# voice_board_kombi.net
KiCad netlist of a schematic drawn in EAGLE
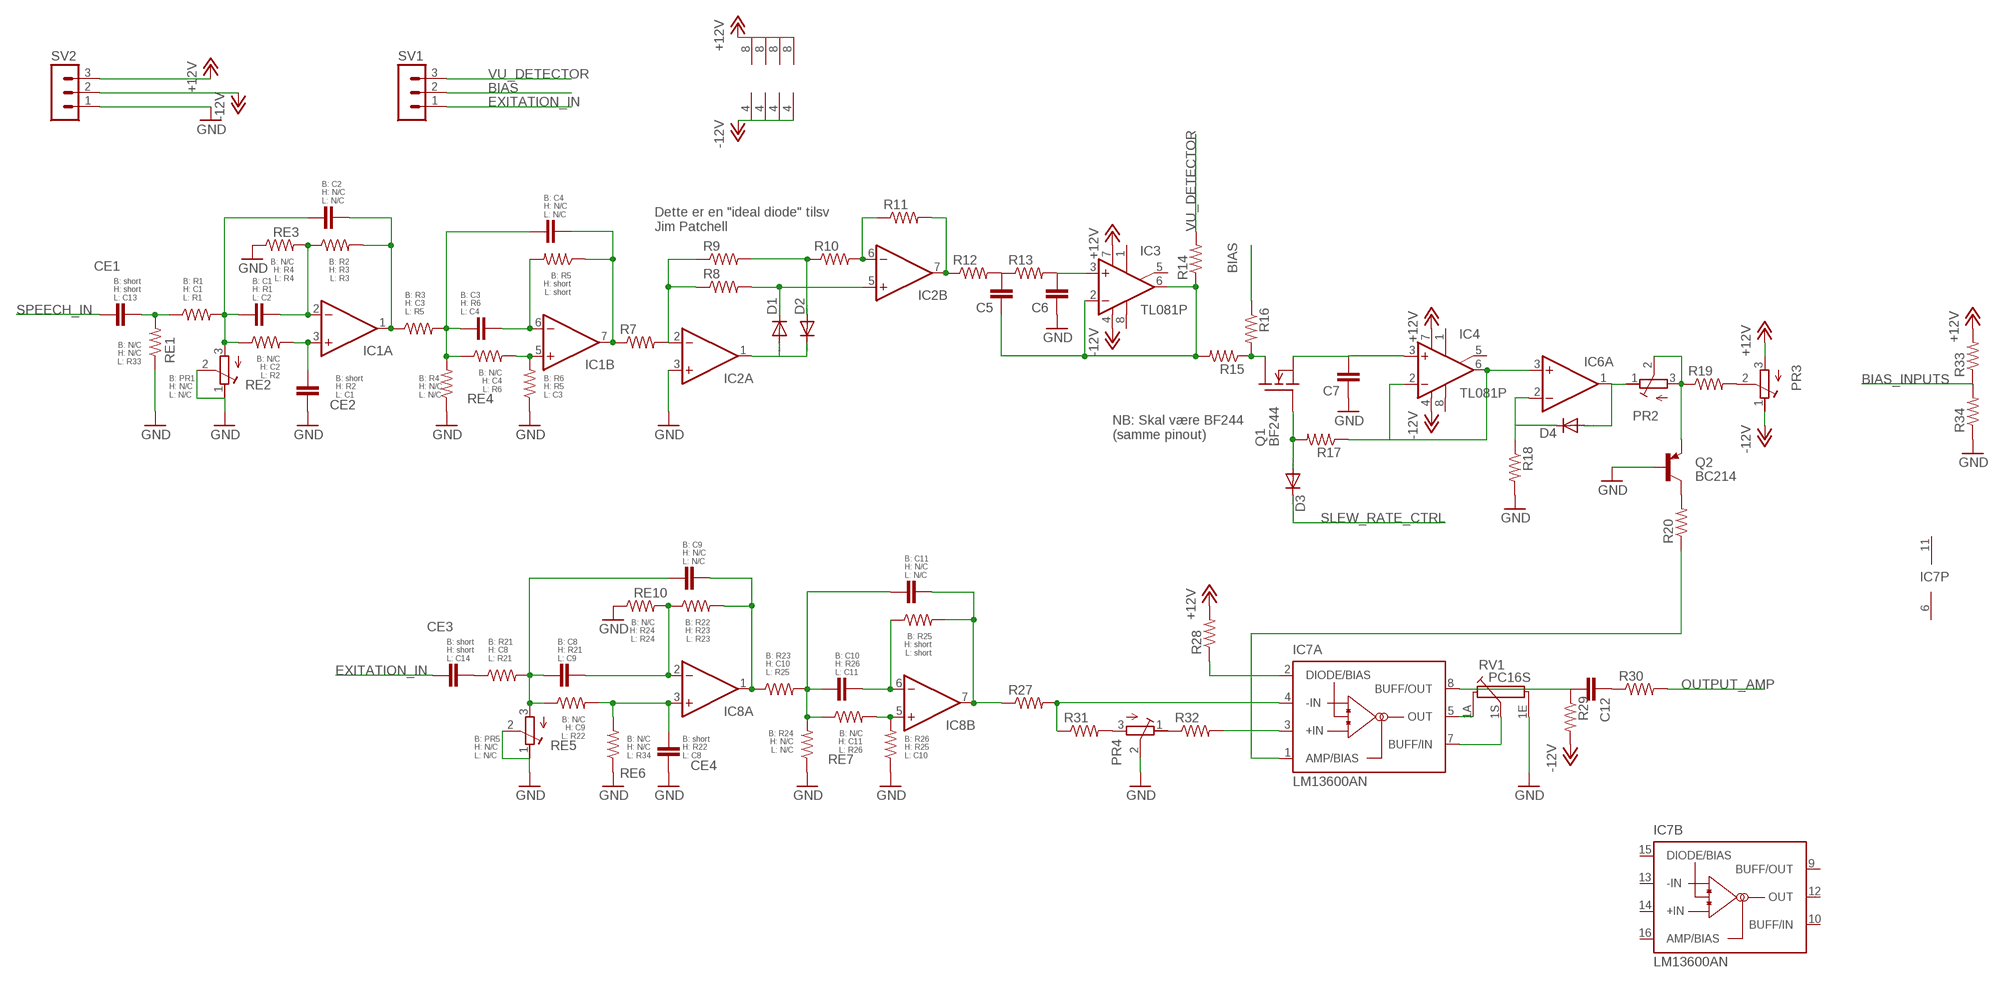
[diagram p0: schematic, sheet 1]

(export (version "E")
  (design (tool "Eeschema 10.0.6"))
  (components
    (comp (ref "C1")
      (value "C-EU050-025X075")
      (footprint "eagle-import:C050-025X075")
      (libsource (lib "eagle-import") (part "C-EU050-025X075"))
    )
    (comp (ref "C2")
      (value "C-EU050-025X075")
      (footprint "eagle-import:C050-025X075")
      (libsource (lib "eagle-import") (part "C-EU050-025X075"))
    )
    (comp (ref "C3")
      (value "C-EU050-025X075")
      (footprint "eagle-import:C050-025X075")
      (libsource (lib "eagle-import") (part "C-EU050-025X075"))
    )
    (comp (ref "C4")
      (value "C-EU050-025X075")
      (footprint "eagle-import:C050-025X075")
      (libsource (lib "eagle-import") (part "C-EU050-025X075"))
    )
    (comp (ref "C5")
      (value "C-EU050-025X075")
      (footprint "eagle-import:C050-025X075")
      (libsource (lib "eagle-import") (part "C-EU050-025X075"))
    )
    (comp (ref "C6")
      (value "C-EU050-025X075")
      (footprint "eagle-import:C050-025X075")
      (libsource (lib "eagle-import") (part "C-EU050-025X075"))
    )
    (comp (ref "C7")
      (value "C-EU050-025X075")
      (footprint "eagle-import:C050-025X075")
      (libsource (lib "eagle-import") (part "C-EU050-025X075"))
    )
    (comp (ref "C8")
      (value "C-EU050-025X075")
      (footprint "eagle-import:C050-025X075")
      (libsource (lib "eagle-import") (part "C-EU050-025X075"))
    )
    (comp (ref "C9")
      (value "C-EU050-025X075")
      (footprint "eagle-import:C050-025X075")
      (libsource (lib "eagle-import") (part "C-EU050-025X075"))
    )
    (comp (ref "C10")
      (value "C-EU050-025X075")
      (footprint "eagle-import:C050-025X075")
      (libsource (lib "eagle-import") (part "C-EU050-025X075"))
    )
    (comp (ref "C11")
      (value "C-EU050-025X075")
      (footprint "eagle-import:C050-025X075")
      (libsource (lib "eagle-import") (part "C-EU050-025X075"))
    )
    (comp (ref "C12")
      (value "C-EU050-025X075")
      (footprint "eagle-import:C050-025X075")
      (libsource (lib "eagle-import") (part "C-EU050-025X075"))
    )
    (comp (ref "CE1")
      (value "C-EU050-025X075")
      (footprint "eagle-import:C050-025X075")
      (libsource (lib "eagle-import") (part "C-EU050-025X075"))
    )
    (comp (ref "CE2")
      (value "C-EU050-025X075")
      (footprint "eagle-import:C050-025X075")
      (libsource (lib "eagle-import") (part "C-EU050-025X075"))
    )
    (comp (ref "CE3")
      (value "C-EU050-025X075")
      (footprint "eagle-import:C050-025X075")
      (libsource (lib "eagle-import") (part "C-EU050-025X075"))
    )
    (comp (ref "CE4")
      (value "C-EU050-025X075")
      (footprint "eagle-import:C050-025X075")
      (libsource (lib "eagle-import") (part "C-EU050-025X075"))
    )
    (comp (ref "D1")
      (value "DIODE-D-5")
      (footprint "eagle-import:D-5")
      (libsource (lib "eagle-import") (part "DIODE-D-5"))
    )
    (comp (ref "D2")
      (value "DIODE-D-5")
      (footprint "eagle-import:D-5")
      (libsource (lib "eagle-import") (part "DIODE-D-5"))
    )
    (comp (ref "D3")
      (value "DIODE-D-5")
      (footprint "eagle-import:D-5")
      (libsource (lib "eagle-import") (part "DIODE-D-5"))
    )
    (comp (ref "D4")
      (value "DIODE-D-5")
      (footprint "eagle-import:D-5")
      (libsource (lib "eagle-import") (part "DIODE-D-5"))
    )
    (comp (ref "IC1")
      (value "TL072P")
      (footprint "eagle-import:DIL08")
      (libsource (lib "eagle-import") (part "TL072P"))
    )
    (comp (ref "IC2")
      (value "TL072P")
      (footprint "eagle-import:DIL08")
      (libsource (lib "eagle-import") (part "TL072P"))
    )
    (comp (ref "IC3")
      (value "TL081P")
      (footprint "eagle-import:DIL08")
      (libsource (lib "eagle-import") (part "TL081P"))
    )
    (comp (ref "IC4")
      (value "TL081P")
      (footprint "eagle-import:DIL08")
      (libsource (lib "eagle-import") (part "TL081P"))
    )
    (comp (ref "IC6")
      (value "TL072P")
      (footprint "eagle-import:DIL08")
      (libsource (lib "eagle-import") (part "TL072P"))
    )
    (comp (ref "IC7")
      (value "LM13600AN")
      (footprint "eagle-import:DIL16")
      (libsource (lib "eagle-import") (part "LM13600NA"))
    )
    (comp (ref "IC8")
      (value "TL072P")
      (footprint "eagle-import:DIL08")
      (libsource (lib "eagle-import") (part "TL072P"))
    )
    (comp (ref "PR1")
      (value "R-TRIMMT93XA")
      (footprint "eagle-import:RTRIMT93XA")
      (libsource (lib "eagle-import") (part "R-TRIMMT93XA"))
    )
    (comp (ref "PR2")
      (value "R-TRIMMT93XA")
      (footprint "eagle-import:RTRIMT93XA")
      (libsource (lib "eagle-import") (part "R-TRIMMT93XA"))
    )
    (comp (ref "PR3")
      (value "R-TRIMMT93XA")
      (footprint "eagle-import:RTRIMT93XA")
      (libsource (lib "eagle-import") (part "R-TRIMMT93XA"))
    )
    (comp (ref "PR4")
      (value "R-TRIMMT93XA")
      (footprint "eagle-import:RTRIMT93XA")
      (libsource (lib "eagle-import") (part "R-TRIMMT93XA"))
    )
    (comp (ref "PR5")
      (value "R-TRIMMT93XA")
      (footprint "eagle-import:RTRIMT93XA")
      (libsource (lib "eagle-import") (part "R-TRIMMT93XA"))
    )
    (comp (ref "Q1")
      (value "BF244")
      (footprint "eagle-import:TO-92")
      (libsource (lib "eagle-import") (part "TN0602N3"))
    )
    (comp (ref "Q2")
      (value "BC214")
      (footprint "eagle-import:TO92")
      (libsource (lib "eagle-import") (part "BC214"))
    )
    (comp (ref "R1")
      (value "R-US_0207/7")
      (footprint "eagle-import:0207_7")
      (libsource (lib "eagle-import") (part "R-US_0207/7"))
    )
    (comp (ref "R2")
      (value "R-US_0207/7")
      (footprint "eagle-import:0207_7")
      (libsource (lib "eagle-import") (part "R-US_0207/7"))
    )
    (comp (ref "R3")
      (value "R-US_0207/7")
      (footprint "eagle-import:0207_7")
      (libsource (lib "eagle-import") (part "R-US_0207/7"))
    )
    (comp (ref "R4")
      (value "R-US_0207/7")
      (footprint "eagle-import:0207_7")
      (libsource (lib "eagle-import") (part "R-US_0207/7"))
    )
    (comp (ref "R5")
      (value "R-US_0207/7")
      (footprint "eagle-import:0207_7")
      (libsource (lib "eagle-import") (part "R-US_0207/7"))
    )
    (comp (ref "R6")
      (value "R-US_0207/7")
      (footprint "eagle-import:0207_7")
      (libsource (lib "eagle-import") (part "R-US_0207/7"))
    )
    (comp (ref "R7")
      (value "R-US_0207/7")
      (footprint "eagle-import:0207_7")
      (libsource (lib "eagle-import") (part "R-US_0207/7"))
    )
    (comp (ref "R8")
      (value "R-US_0207/7")
      (footprint "eagle-import:0207_7")
      (libsource (lib "eagle-import") (part "R-US_0207/7"))
    )
    (comp (ref "R9")
      (value "R-US_0207/7")
      (footprint "eagle-import:0207_7")
      (libsource (lib "eagle-import") (part "R-US_0207/7"))
    )
    (comp (ref "R10")
      (value "R-US_0207/7")
      (footprint "eagle-import:0207_7")
      (libsource (lib "eagle-import") (part "R-US_0207/7"))
    )
    (comp (ref "R11")
      (value "R-US_0207/7")
      (footprint "eagle-import:0207_7")
      (libsource (lib "eagle-import") (part "R-US_0207/7"))
    )
    (comp (ref "R12")
      (value "R-US_0207/7")
      (footprint "eagle-import:0207_7")
      (libsource (lib "eagle-import") (part "R-US_0207/7"))
    )
    (comp (ref "R13")
      (value "R-US_0207/7")
      (footprint "eagle-import:0207_7")
      (libsource (lib "eagle-import") (part "R-US_0207/7"))
    )
    (comp (ref "R14")
      (value "R-US_0207/7")
      (footprint "eagle-import:0207_7")
      (libsource (lib "eagle-import") (part "R-US_0207/7"))
    )
    (comp (ref "R15")
      (value "R-US_0207/7")
      (footprint "eagle-import:0207_7")
      (libsource (lib "eagle-import") (part "R-US_0207/7"))
    )
    (comp (ref "R16")
      (value "R-US_0207/7")
      (footprint "eagle-import:0207_7")
      (libsource (lib "eagle-import") (part "R-US_0207/7"))
    )
    (comp (ref "R17")
      (value "R-US_0207/7")
      (footprint "eagle-import:0207_7")
      (libsource (lib "eagle-import") (part "R-US_0207/7"))
    )
    (comp (ref "R18")
      (value "R-US_0207/7")
      (footprint "eagle-import:0207_7")
      (libsource (lib "eagle-import") (part "R-US_0207/7"))
    )
    (comp (ref "R19")
      (value "R-US_0207/7")
      (footprint "eagle-import:0207_7")
      (libsource (lib "eagle-import") (part "R-US_0207/7"))
    )
    (comp (ref "R20")
      (value "R-US_0207/7")
      (footprint "eagle-import:0207_7")
      (libsource (lib "eagle-import") (part "R-US_0207/7"))
    )
    (comp (ref "R21")
      (value "R-US_0207/7")
      (footprint "eagle-import:0207_7")
      (libsource (lib "eagle-import") (part "R-US_0207/7"))
    )
    (comp (ref "R22")
      (value "R-US_0207/7")
      (footprint "eagle-import:0207_7")
      (libsource (lib "eagle-import") (part "R-US_0207/7"))
    )
    (comp (ref "R23")
      (value "R-US_0207/7")
      (footprint "eagle-import:0207_7")
      (libsource (lib "eagle-import") (part "R-US_0207/7"))
    )
    (comp (ref "R24")
      (value "R-US_0207/7")
      (footprint "eagle-import:0207_7")
      (libsource (lib "eagle-import") (part "R-US_0207/7"))
    )
    (comp (ref "R25")
      (value "R-US_0207/7")
      (footprint "eagle-import:0207_7")
      (libsource (lib "eagle-import") (part "R-US_0207/7"))
    )
    (comp (ref "R26")
      (value "R-US_0207/7")
      (footprint "eagle-import:0207_7")
      (libsource (lib "eagle-import") (part "R-US_0207/7"))
    )
    (comp (ref "R27")
      (value "R-US_0207/7")
      (footprint "eagle-import:0207_7")
      (libsource (lib "eagle-import") (part "R-US_0207/7"))
    )
    (comp (ref "R28")
      (value "R-US_0207/7")
      (footprint "eagle-import:0207_7")
      (libsource (lib "eagle-import") (part "R-US_0207/7"))
    )
    (comp (ref "R29")
      (value "R-US_0207/7")
      (footprint "eagle-import:0207_7")
      (libsource (lib "eagle-import") (part "R-US_0207/7"))
    )
    (comp (ref "R30")
      (value "R-US_0207/7")
      (footprint "eagle-import:0207_7")
      (libsource (lib "eagle-import") (part "R-US_0207/7"))
    )
    (comp (ref "R31")
      (value "R-US_0207/7")
      (footprint "eagle-import:0207_7")
      (libsource (lib "eagle-import") (part "R-US_0207/7"))
    )
    (comp (ref "R32")
      (value "R-US_0207/7")
      (footprint "eagle-import:0207_7")
      (libsource (lib "eagle-import") (part "R-US_0207/7"))
    )
    (comp (ref "R33")
      (value "R-US_0207/7")
      (footprint "eagle-import:0207_7")
      (libsource (lib "eagle-import") (part "R-US_0207/7"))
    )
    (comp (ref "R34")
      (value "R-US_0207/7")
      (footprint "eagle-import:0207_7")
      (libsource (lib "eagle-import") (part "R-US_0207/7"))
    )
    (comp (ref "RE1")
      (value "R-US_0207/7")
      (footprint "eagle-import:0207_7")
      (libsource (lib "eagle-import") (part "R-US_0207/7"))
    )
    (comp (ref "RE2")
      (value "R-US_0207/7")
      (footprint "eagle-import:0207_7")
      (libsource (lib "eagle-import") (part "R-US_0207/7"))
    )
    (comp (ref "RE3")
      (value "R-US_0207/7")
      (footprint "eagle-import:0207_7")
      (libsource (lib "eagle-import") (part "R-US_0207/7"))
    )
    (comp (ref "RE4")
      (value "R-US_0207/7")
      (footprint "eagle-import:0207_7")
      (libsource (lib "eagle-import") (part "R-US_0207/7"))
    )
    (comp (ref "RE5")
      (value "R-US_0207/7")
      (footprint "eagle-import:0207_7")
      (libsource (lib "eagle-import") (part "R-US_0207/7"))
    )
    (comp (ref "RE6")
      (value "R-US_0207/7")
      (footprint "eagle-import:0207_7")
      (libsource (lib "eagle-import") (part "R-US_0207/7"))
    )
    (comp (ref "RE7")
      (value "R-US_0207/7")
      (footprint "eagle-import:0207_7")
      (libsource (lib "eagle-import") (part "R-US_0207/7"))
    )
    (comp (ref "RE10")
      (value "R-US_0207/7")
      (footprint "eagle-import:0207_7")
      (libsource (lib "eagle-import") (part "R-US_0207/7"))
    )
    (comp (ref "RV1")
      (value "PC16S")
      (footprint "eagle-import:PC16S")
      (libsource (lib "eagle-import") (part "PC16S"))
    )
    (comp (ref "SV1")
      (value "MA03-1")
      (footprint "eagle-import:MA03-1")
      (libsource (lib "eagle-import") (part "MA03-1"))
    )
    (comp (ref "SV2")
      (value "MA03-1")
      (footprint "eagle-import:MA03-1")
      (libsource (lib "eagle-import") (part "MA03-1"))
    )
  )
  (nets
    (net (code "1") (name "+12V") (class "Default")
      (node (ref "IC1") (pin "8") (pinfunction "V+_8") (pintype "power_in"))
      (node (ref "IC2") (pin "8") (pinfunction "V+_8") (pintype "power_in"))
      (node (ref "IC3") (pin "7") (pinfunction "V+_7") (pintype "power_in"))
      (node (ref "IC4") (pin "7") (pinfunction "V+_7") (pintype "power_in"))
      (node (ref "IC6") (pin "8") (pinfunction "V+_8") (pintype "power_in"))
      (node (ref "IC8") (pin "8") (pinfunction "V+_8") (pintype "power_in"))
      (node (ref "PR3") (pin "3") (pinfunction "A_3") (pintype "passive"))
      (node (ref "R28") (pin "2") (pinfunction "2_2") (pintype "passive"))
      (node (ref "R33") (pin "2") (pinfunction "2_2") (pintype "passive"))
      (node (ref "SV2") (pin "3") (pinfunction "3_3") (pintype "passive"))
    )
    (net (code "2") (name "-12V") (class "Default")
      (node (ref "IC1") (pin "4") (pinfunction "V-_4") (pintype "power_in"))
      (node (ref "IC2") (pin "4") (pinfunction "V-_4") (pintype "power_in"))
      (node (ref "IC3") (pin "4") (pinfunction "V-_4") (pintype "power_in"))
      (node (ref "IC4") (pin "4") (pinfunction "V-_4") (pintype "power_in"))
      (node (ref "IC6") (pin "4") (pinfunction "V-_4") (pintype "power_in"))
      (node (ref "IC8") (pin "4") (pinfunction "V-_4") (pintype "power_in"))
      (node (ref "PR3") (pin "1") (pinfunction "E_1") (pintype "passive"))
      (node (ref "R29") (pin "2") (pinfunction "2_2") (pintype "passive"))
      (node (ref "SV2") (pin "2") (pinfunction "2_2") (pintype "passive"))
    )
    (net (code "3") (name "/BIAS") (class "Default")
      (node (ref "R16") (pin "1") (pinfunction "1_1") (pintype "passive"))
      (node (ref "SV1") (pin "2") (pinfunction "2_2") (pintype "passive"))
    )
    (net (code "4") (name "/BIAS_INPUTS") (class "Default")
      (node (ref "R33") (pin "1") (pinfunction "1_1") (pintype "passive"))
      (node (ref "R34") (pin "2") (pinfunction "2_2") (pintype "passive"))
    )
    (net (code "5") (name "/EXITATION_IN") (class "Default")
      (node (ref "CE3") (pin "1") (pinfunction "1_1") (pintype "passive"))
      (node (ref "SV1") (pin "1") (pinfunction "1_1") (pintype "passive"))
    )
    (net (code "6") (name "/OUTPUT_AMP") (class "Default")
      (node (ref "R30") (pin "2") (pinfunction "2_2") (pintype "passive"))
    )
    (net (code "7") (name "/SLEW_RATE_CTRL") (class "Default")
      (node (ref "D3") (pin "C") (pinfunction "C_C") (pintype "passive"))
    )
    (net (code "8") (name "/SPEECH_IN") (class "Default")
      (node (ref "CE1") (pin "1") (pinfunction "1_1") (pintype "passive"))
    )
    (net (code "9") (name "/V+") (class "Default")
      (node (ref "IC7") (pin "11") (pinfunction "V+_11") (pintype "power_in"))
    )
    (net (code "10") (name "/V-") (class "Default")
      (node (ref "IC7") (pin "6") (pinfunction "V-_6") (pintype "power_in"))
    )
    (net (code "11") (name "/VU_DETECTOR") (class "Default")
      (node (ref "R14") (pin "2") (pinfunction "2_2") (pintype "passive"))
      (node (ref "SV1") (pin "3") (pinfunction "3_3") (pintype "passive"))
    )
    (net (code "12") (name "GND") (class "Default")
      (node (ref "C6") (pin "1") (pinfunction "1_1") (pintype "passive"))
      (node (ref "C7") (pin "1") (pinfunction "1_1") (pintype "passive"))
      (node (ref "CE2") (pin "1") (pinfunction "1_1") (pintype "passive"))
      (node (ref "CE4") (pin "1") (pinfunction "1_1") (pintype "passive"))
      (node (ref "IC2") (pin "3") (pinfunction "+IN_3") (pintype "input"))
      (node (ref "PR1") (pin "1") (pinfunction "E_1") (pintype "passive"))
      (node (ref "PR1") (pin "2") (pinfunction "S_2") (pintype "passive"))
      (node (ref "PR4") (pin "2") (pinfunction "S_2") (pintype "passive"))
      (node (ref "PR5") (pin "1") (pinfunction "E_1") (pintype "passive"))
      (node (ref "PR5") (pin "2") (pinfunction "S_2") (pintype "passive"))
      (node (ref "Q2") (pin "2") (pinfunction "B_2") (pintype "passive"))
      (node (ref "R18") (pin "2") (pinfunction "2_2") (pintype "passive"))
      (node (ref "R24") (pin "1") (pinfunction "1_1") (pintype "passive"))
      (node (ref "R26") (pin "1") (pinfunction "1_1") (pintype "passive"))
      (node (ref "R34") (pin "1") (pinfunction "1_1") (pintype "passive"))
      (node (ref "R4") (pin "1") (pinfunction "1_1") (pintype "passive"))
      (node (ref "R6") (pin "1") (pinfunction "1_1") (pintype "passive"))
      (node (ref "RE1") (pin "1") (pinfunction "1_1") (pintype "passive"))
      (node (ref "RE10") (pin "1") (pinfunction "1_1") (pintype "passive"))
      (node (ref "RE3") (pin "1") (pinfunction "1_1") (pintype "passive"))
      (node (ref "RE6") (pin "1") (pinfunction "1_1") (pintype "passive"))
      (node (ref "RV1") (pin "1E") (pinfunction "1E_1E") (pintype "passive"))
      (node (ref "SV2") (pin "1") (pinfunction "1_1") (pintype "passive"))
    )
    (net (code "13") (name "Net-(C3-Pad1)") (class "Default")
      (node (ref "C3") (pin "1") (pinfunction "1_1") (pintype "passive"))
      (node (ref "C4") (pin "1") (pinfunction "1_1") (pintype "passive"))
      (node (ref "R3") (pin "2") (pinfunction "2_2") (pintype "passive"))
      (node (ref "R4") (pin "2") (pinfunction "2_2") (pintype "passive"))
      (node (ref "RE4") (pin "1") (pinfunction "1_1") (pintype "passive"))
    )
    (net (code "14") (name "Net-(C5-Pad2)") (class "Default")
      (node (ref "C5") (pin "2") (pinfunction "2_2") (pintype "passive"))
      (node (ref "R12") (pin "2") (pinfunction "2_2") (pintype "passive"))
      (node (ref "R13") (pin "1") (pinfunction "1_1") (pintype "passive"))
    )
    (net (code "15") (name "Net-(C10-Pad2)") (class "Default")
      (node (ref "C10") (pin "2") (pinfunction "2_2") (pintype "passive"))
      (node (ref "C11") (pin "2") (pinfunction "2_2") (pintype "passive"))
      (node (ref "R23") (pin "2") (pinfunction "2_2") (pintype "passive"))
      (node (ref "R24") (pin "2") (pinfunction "2_2") (pintype "passive"))
      (node (ref "RE7") (pin "1") (pinfunction "1_1") (pintype "passive"))
    )
    (net (code "16") (name "Net-(C12-Pad1)") (class "Default")
      (node (ref "C12") (pin "1") (pinfunction "1_1") (pintype "passive"))
      (node (ref "R30") (pin "1") (pinfunction "1_1") (pintype "passive"))
    )
    (net (code "17") (name "Net-(CE1-Pad2)") (class "Default")
      (node (ref "CE1") (pin "2") (pinfunction "2_2") (pintype "passive"))
      (node (ref "R1") (pin "1") (pinfunction "1_1") (pintype "passive"))
      (node (ref "RE1") (pin "2") (pinfunction "2_2") (pintype "passive"))
    )
    (net (code "18") (name "Net-(CE3-Pad2)") (class "Default")
      (node (ref "CE3") (pin "2") (pinfunction "2_2") (pintype "passive"))
      (node (ref "R21") (pin "1") (pinfunction "1_1") (pintype "passive"))
    )
    (net (code "19") (name "Net-(D2-PadA)") (class "Default")
      (node (ref "D2") (pin "A") (pinfunction "A_A") (pintype "passive"))
      (node (ref "R10") (pin "1") (pinfunction "1_1") (pintype "passive"))
      (node (ref "R9") (pin "2") (pinfunction "2_2") (pintype "passive"))
    )
    (net (code "20") (name "Net-(IC1A-+IN)") (class "Default")
      (node (ref "CE2") (pin "2") (pinfunction "2_2") (pintype "passive"))
      (node (ref "IC1") (pin "3") (pinfunction "+IN_3") (pintype "input"))
      (node (ref "RE2") (pin "2") (pinfunction "2_2") (pintype "passive"))
    )
    (net (code "21") (name "Net-(IC1A--IN)") (class "Default")
      (node (ref "C1") (pin "2") (pinfunction "2_2") (pintype "passive"))
      (node (ref "IC1") (pin "2") (pinfunction "-IN_2") (pintype "input"))
      (node (ref "R2") (pin "1") (pinfunction "1_1") (pintype "passive"))
      (node (ref "RE3") (pin "2") (pinfunction "2_2") (pintype "passive"))
    )
    (net (code "22") (name "Net-(IC1A-OUT)") (class "Default")
      (node (ref "C2") (pin "2") (pinfunction "2_2") (pintype "passive"))
      (node (ref "IC1") (pin "1") (pinfunction "OUT_1") (pintype "output"))
      (node (ref "R2") (pin "2") (pinfunction "2_2") (pintype "passive"))
      (node (ref "R3") (pin "1") (pinfunction "1_1") (pintype "passive"))
    )
    (net (code "23") (name "Net-(IC1B-+IN)") (class "Default")
      (node (ref "IC1") (pin "5") (pinfunction "+IN_5") (pintype "input"))
      (node (ref "R6") (pin "2") (pinfunction "2_2") (pintype "passive"))
      (node (ref "RE4") (pin "2") (pinfunction "2_2") (pintype "passive"))
    )
    (net (code "24") (name "Net-(IC1B--IN)") (class "Default")
      (node (ref "C3") (pin "2") (pinfunction "2_2") (pintype "passive"))
      (node (ref "IC1") (pin "6") (pinfunction "-IN_6") (pintype "input"))
      (node (ref "R5") (pin "2") (pinfunction "2_2") (pintype "passive"))
    )
    (net (code "25") (name "Net-(IC1B-OUT)") (class "Default")
      (node (ref "C4") (pin "2") (pinfunction "2_2") (pintype "passive"))
      (node (ref "IC1") (pin "7") (pinfunction "OUT_7") (pintype "output"))
      (node (ref "R5") (pin "1") (pinfunction "1_1") (pintype "passive"))
      (node (ref "R7") (pin "1") (pinfunction "1_1") (pintype "passive"))
    )
    (net (code "26") (name "Net-(IC2A--IN)") (class "Default")
      (node (ref "IC2") (pin "2") (pinfunction "-IN_2") (pintype "input"))
      (node (ref "R7") (pin "2") (pinfunction "2_2") (pintype "passive"))
      (node (ref "R8") (pin "1") (pinfunction "1_1") (pintype "passive"))
      (node (ref "R9") (pin "1") (pinfunction "1_1") (pintype "passive"))
    )
    (net (code "27") (name "Net-(IC2A-OUT)") (class "Default")
      (node (ref "D1") (pin "A") (pinfunction "A_A") (pintype "passive"))
      (node (ref "D2") (pin "C") (pinfunction "C_C") (pintype "passive"))
      (node (ref "IC2") (pin "1") (pinfunction "OUT_1") (pintype "output"))
    )
    (net (code "28") (name "Net-(IC2B-+IN)") (class "Default")
      (node (ref "D1") (pin "C") (pinfunction "C_C") (pintype "passive"))
      (node (ref "IC2") (pin "5") (pinfunction "+IN_5") (pintype "input"))
      (node (ref "R8") (pin "2") (pinfunction "2_2") (pintype "passive"))
    )
    (net (code "29") (name "Net-(IC2B--IN)") (class "Default")
      (node (ref "IC2") (pin "6") (pinfunction "-IN_6") (pintype "input"))
      (node (ref "R10") (pin "2") (pinfunction "2_2") (pintype "passive"))
      (node (ref "R11") (pin "1") (pinfunction "1_1") (pintype "passive"))
    )
    (net (code "30") (name "Net-(IC2B-OUT)") (class "Default")
      (node (ref "IC2") (pin "7") (pinfunction "OUT_7") (pintype "output"))
      (node (ref "R11") (pin "2") (pinfunction "2_2") (pintype "passive"))
      (node (ref "R12") (pin "1") (pinfunction "1_1") (pintype "passive"))
    )
    (net (code "31") (name "Net-(IC3-+IN)") (class "Default")
      (node (ref "C6") (pin "2") (pinfunction "2_2") (pintype "passive"))
      (node (ref "IC3") (pin "3") (pinfunction "+IN_3") (pintype "input"))
      (node (ref "R13") (pin "2") (pinfunction "2_2") (pintype "passive"))
    )
    (net (code "32") (name "Net-(IC3--IN)") (class "Default")
      (node (ref "C5") (pin "1") (pinfunction "1_1") (pintype "passive"))
      (node (ref "IC3") (pin "2") (pinfunction "-IN_2") (pintype "input"))
      (node (ref "IC3") (pin "6") (pinfunction "OUT_6") (pintype "output"))
      (node (ref "R14") (pin "1") (pinfunction "1_1") (pintype "passive"))
      (node (ref "R15") (pin "2") (pinfunction "2_2") (pintype "passive"))
    )
    (net (code "33") (name "Net-(IC4-+IN)") (class "Default")
      (node (ref "C7") (pin "2") (pinfunction "2_2") (pintype "passive"))
      (node (ref "IC4") (pin "3") (pinfunction "+IN_3") (pintype "input"))
      (node (ref "Q1") (pin "1") (pinfunction "S_1") (pintype "passive"))
    )
    (net (code "34") (name "Net-(IC4--IN)") (class "Default")
      (node (ref "IC4") (pin "2") (pinfunction "-IN_2") (pintype "input"))
      (node (ref "IC4") (pin "6") (pinfunction "OUT_6") (pintype "output"))
      (node (ref "IC6") (pin "3") (pinfunction "+IN_3") (pintype "input"))
      (node (ref "R17") (pin "1") (pinfunction "1_1") (pintype "passive"))
    )
    (net (code "35") (name "Net-(IC6A--IN)") (class "Default")
      (node (ref "D4") (pin "C") (pinfunction "C_C") (pintype "passive"))
      (node (ref "IC6") (pin "2") (pinfunction "-IN_2") (pintype "input"))
      (node (ref "R18") (pin "1") (pinfunction "1_1") (pintype "passive"))
    )
    (net (code "36") (name "Net-(IC6A-OUT)") (class "Default")
      (node (ref "D4") (pin "A") (pinfunction "A_A") (pintype "passive"))
      (node (ref "IC6") (pin "1") (pinfunction "OUT_1") (pintype "output"))
      (node (ref "PR2") (pin "1") (pinfunction "E_1") (pintype "passive"))
    )
    (net (code "37") (name "Net-(IC7A-+IN)") (class "Default")
      (node (ref "IC7") (pin "3") (pinfunction "+IN_3") (pintype "input"))
      (node (ref "R32") (pin "2") (pinfunction "2_2") (pintype "passive"))
    )
    (net (code "38") (name "Net-(IC7A--IN)") (class "Default")
      (node (ref "IC7") (pin "4") (pinfunction "-IN_4") (pintype "input"))
      (node (ref "R27") (pin "2") (pinfunction "2_2") (pintype "passive"))
      (node (ref "R31") (pin "1") (pinfunction "1_1") (pintype "passive"))
    )
    (net (code "39") (name "Net-(IC7A-AMP{slash}BIAS)") (class "Default")
      (node (ref "IC7") (pin "1") (pinfunction "AMP/BIAS_1") (pintype "passive"))
      (node (ref "R20") (pin "1") (pinfunction "1_1") (pintype "passive"))
    )
    (net (code "40") (name "Net-(IC7A-BUFF{slash}IN)") (class "Default")
      (node (ref "IC7") (pin "7") (pinfunction "BUFF/IN_7") (pintype "input"))
      (node (ref "RV1") (pin "1S") (pinfunction "1S_1S") (pintype "passive"))
    )
    (net (code "41") (name "Net-(IC7A-BUFF{slash}OUT)") (class "Default")
      (node (ref "C12") (pin "2") (pinfunction "2_2") (pintype "passive"))
      (node (ref "IC7") (pin "8") (pinfunction "BUFF/OUT_8") (pintype "output"))
      (node (ref "R29") (pin "1") (pinfunction "1_1") (pintype "passive"))
    )
    (net (code "42") (name "Net-(IC7A-DIODE{slash}BIAS)") (class "Default")
      (node (ref "IC7") (pin "2") (pinfunction "DIODE/BIAS_2") (pintype "passive"))
      (node (ref "R28") (pin "1") (pinfunction "1_1") (pintype "passive"))
    )
    (net (code "43") (name "Net-(IC7A-OUT)") (class "Default")
      (node (ref "IC7") (pin "5") (pinfunction "OUT_5") (pintype "output"))
      (node (ref "RV1") (pin "1A") (pinfunction "1A_1A") (pintype "passive"))
    )
    (net (code "44") (name "Net-(IC8A-+IN)") (class "Default")
      (node (ref "CE4") (pin "2") (pinfunction "2_2") (pintype "passive"))
      (node (ref "IC8") (pin "3") (pinfunction "+IN_3") (pintype "input"))
      (node (ref "RE5") (pin "2") (pinfunction "2_2") (pintype "passive"))
      (node (ref "RE6") (pin "2") (pinfunction "2_2") (pintype "passive"))
    )
    (net (code "45") (name "Net-(IC8A--IN)") (class "Default")
      (node (ref "C8") (pin "1") (pinfunction "1_1") (pintype "passive"))
      (node (ref "IC8") (pin "2") (pinfunction "-IN_2") (pintype "input"))
      (node (ref "R22") (pin "1") (pinfunction "1_1") (pintype "passive"))
      (node (ref "RE10") (pin "2") (pinfunction "2_2") (pintype "passive"))
    )
    (net (code "46") (name "Net-(IC8A-OUT)") (class "Default")
      (node (ref "C9") (pin "1") (pinfunction "1_1") (pintype "passive"))
      (node (ref "IC8") (pin "1") (pinfunction "OUT_1") (pintype "output"))
      (node (ref "R22") (pin "2") (pinfunction "2_2") (pintype "passive"))
      (node (ref "R23") (pin "1") (pinfunction "1_1") (pintype "passive"))
    )
    (net (code "47") (name "Net-(IC8B-+IN)") (class "Default")
      (node (ref "IC8") (pin "5") (pinfunction "+IN_5") (pintype "input"))
      (node (ref "R26") (pin "2") (pinfunction "2_2") (pintype "passive"))
      (node (ref "RE7") (pin "2") (pinfunction "2_2") (pintype "passive"))
    )
    (net (code "48") (name "Net-(IC8B--IN)") (class "Default")
      (node (ref "C10") (pin "1") (pinfunction "1_1") (pintype "passive"))
      (node (ref "IC8") (pin "6") (pinfunction "-IN_6") (pintype "input"))
      (node (ref "R25") (pin "1") (pinfunction "1_1") (pintype "passive"))
    )
    (net (code "49") (name "Net-(IC8B-OUT)") (class "Default")
      (node (ref "C11") (pin "1") (pinfunction "1_1") (pintype "passive"))
      (node (ref "IC8") (pin "7") (pinfunction "OUT_7") (pintype "output"))
      (node (ref "R25") (pin "2") (pinfunction "2_2") (pintype "passive"))
      (node (ref "R27") (pin "1") (pinfunction "1_1") (pintype "passive"))
    )
    (net (code "50") (name "Net-(PR1-A)") (class "Default")
      (node (ref "C1") (pin "1") (pinfunction "1_1") (pintype "passive"))
      (node (ref "C2") (pin "1") (pinfunction "1_1") (pintype "passive"))
      (node (ref "PR1") (pin "3") (pinfunction "A_3") (pintype "passive"))
      (node (ref "R1") (pin "2") (pinfunction "2_2") (pintype "passive"))
      (node (ref "RE2") (pin "1") (pinfunction "1_1") (pintype "passive"))
    )
    (net (code "51") (name "Net-(PR2-A)") (class "Default")
      (node (ref "PR2") (pin "2") (pinfunction "S_2") (pintype "passive"))
      (node (ref "PR2") (pin "3") (pinfunction "A_3") (pintype "passive"))
      (node (ref "Q2") (pin "1") (pinfunction "E_1") (pintype "passive"))
      (node (ref "R19") (pin "1") (pinfunction "1_1") (pintype "passive"))
    )
    (net (code "52") (name "Net-(PR3-S)") (class "Default")
      (node (ref "PR3") (pin "2") (pinfunction "S_2") (pintype "passive"))
      (node (ref "R19") (pin "2") (pinfunction "2_2") (pintype "passive"))
    )
    (net (code "53") (name "Net-(PR4-A)") (class "Default")
      (node (ref "PR4") (pin "3") (pinfunction "A_3") (pintype "passive"))
      (node (ref "R31") (pin "2") (pinfunction "2_2") (pintype "passive"))
    )
    (net (code "54") (name "Net-(PR4-E)") (class "Default")
      (node (ref "PR4") (pin "1") (pinfunction "E_1") (pintype "passive"))
      (node (ref "R32") (pin "1") (pinfunction "1_1") (pintype "passive"))
    )
    (net (code "55") (name "Net-(PR5-A)") (class "Default")
      (node (ref "C8") (pin "2") (pinfunction "2_2") (pintype "passive"))
      (node (ref "C9") (pin "2") (pinfunction "2_2") (pintype "passive"))
      (node (ref "PR5") (pin "3") (pinfunction "A_3") (pintype "passive"))
      (node (ref "R21") (pin "2") (pinfunction "2_2") (pintype "passive"))
      (node (ref "RE5") (pin "1") (pinfunction "1_1") (pintype "passive"))
    )
    (net (code "56") (name "Net-(Q1-D)") (class "Default")
      (node (ref "Q1") (pin "3") (pinfunction "D_3") (pintype "passive"))
      (node (ref "R15") (pin "1") (pinfunction "1_1") (pintype "passive"))
      (node (ref "R16") (pin "2") (pinfunction "2_2") (pintype "passive"))
    )
    (net (code "57") (name "Net-(Q1-G)") (class "Default")
      (node (ref "D3") (pin "A") (pinfunction "A_A") (pintype "passive"))
      (node (ref "Q1") (pin "2") (pinfunction "G_2") (pintype "passive"))
      (node (ref "R17") (pin "2") (pinfunction "2_2") (pintype "passive"))
    )
    (net (code "58") (name "Net-(Q2-C)") (class "Default")
      (node (ref "Q2") (pin "3") (pinfunction "C_3") (pintype "passive"))
      (node (ref "R20") (pin "2") (pinfunction "2_2") (pintype "passive"))
    )
    (net (code "59") (name "unconnected-(IC3-ON1-Pad1)") (class "Default")
      (node (ref "IC3") (pin "1") (pinfunction "ON1_1") (pintype "passive"))
    )
    (net (code "60") (name "unconnected-(IC3-ON2-Pad5)") (class "Default")
      (node (ref "IC3") (pin "5") (pinfunction "ON2_5") (pintype "passive"))
    )
    (net (code "61") (name "unconnected-(IC3-OPT-Pad8)") (class "Default")
      (node (ref "IC3") (pin "8") (pinfunction "OPT_8") (pintype "passive"))
    )
    (net (code "62") (name "unconnected-(IC4-ON1-Pad1)") (class "Default")
      (node (ref "IC4") (pin "1") (pinfunction "ON1_1") (pintype "passive"))
    )
    (net (code "63") (name "unconnected-(IC4-ON2-Pad5)") (class "Default")
      (node (ref "IC4") (pin "5") (pinfunction "ON2_5") (pintype "passive"))
    )
    (net (code "64") (name "unconnected-(IC4-OPT-Pad8)") (class "Default")
      (node (ref "IC4") (pin "8") (pinfunction "OPT_8") (pintype "passive"))
    )
    (net (code "65") (name "unconnected-(IC7B-+IN-Pad14)") (class "Default")
      (node (ref "IC7") (pin "14") (pinfunction "+IN_14") (pintype "input"))
    )
    (net (code "66") (name "unconnected-(IC7B--IN-Pad13)") (class "Default")
      (node (ref "IC7") (pin "13") (pinfunction "-IN_13") (pintype "input"))
    )
    (net (code "67") (name "unconnected-(IC7B-AMP{slash}BIAS-Pad16)") (class "Default")
      (node (ref "IC7") (pin "16") (pinfunction "AMP/BIAS_16") (pintype "passive"))
    )
    (net (code "68") (name "unconnected-(IC7B-BUFF{slash}IN-Pad10)") (class "Default")
      (node (ref "IC7") (pin "10") (pinfunction "BUFF/IN_10") (pintype "input"))
    )
    (net (code "69") (name "unconnected-(IC7B-BUFF{slash}OUT-Pad9)") (class "Default")
      (node (ref "IC7") (pin "9") (pinfunction "BUFF/OUT_9") (pintype "output"))
    )
    (net (code "70") (name "unconnected-(IC7B-DIODE{slash}BIAS-Pad15)") (class "Default")
      (node (ref "IC7") (pin "15") (pinfunction "DIODE/BIAS_15") (pintype "passive"))
    )
    (net (code "71") (name "unconnected-(IC7B-OUT-Pad12)") (class "Default")
      (node (ref "IC7") (pin "12") (pinfunction "OUT_12") (pintype "output"))
    )
  )
)
